# Raspberry-Board.net
KiCad netlist of a schematic drawn in EAGLE
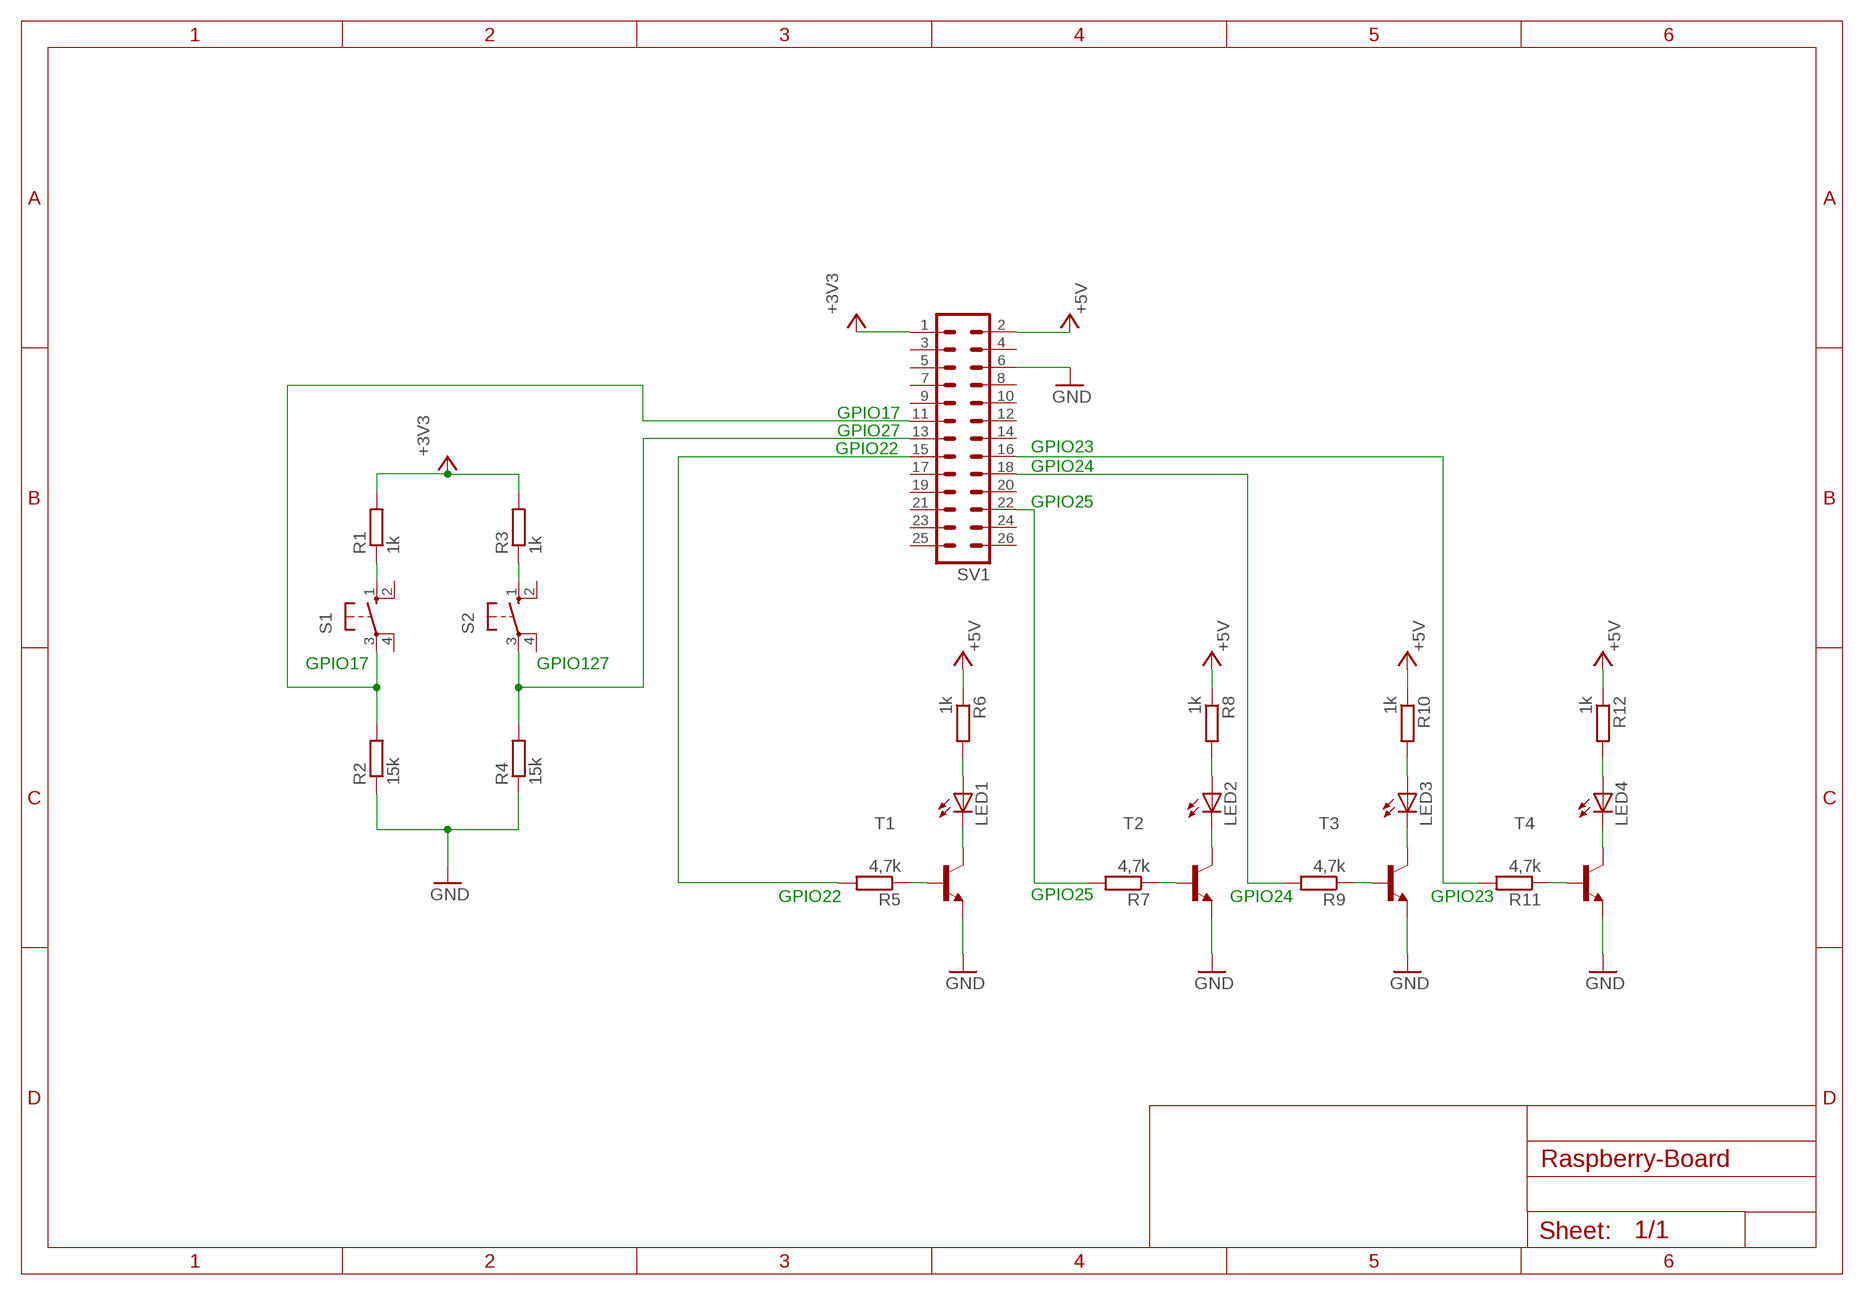
[diagram p0: schematic, sheet 1]

(export (version "E")
  (design (tool "Eeschema 10.0.6"))
  (components
    (comp (ref "LED1")
      (value "LEDCHIPLED_1206")
      (footprint "eagle-import:CHIPLED_1206")
      (libsource (lib "eagle-import") (part "LEDCHIPLED_1206"))
    )
    (comp (ref "LED2")
      (value "LEDCHIPLED_1206")
      (footprint "eagle-import:CHIPLED_1206")
      (libsource (lib "eagle-import") (part "LEDCHIPLED_1206"))
    )
    (comp (ref "LED3")
      (value "LEDCHIPLED_1206")
      (footprint "eagle-import:CHIPLED_1206")
      (libsource (lib "eagle-import") (part "LEDCHIPLED_1206"))
    )
    (comp (ref "LED4")
      (value "LEDCHIPLED_1206")
      (footprint "eagle-import:CHIPLED_1206")
      (libsource (lib "eagle-import") (part "LEDCHIPLED_1206"))
    )
    (comp (ref "R1")
      (value "1k")
      (footprint "eagle-import:R0805")
      (libsource (lib "eagle-import") (part "R-EU_R0805"))
    )
    (comp (ref "R2")
      (value "15k")
      (footprint "eagle-import:R0805")
      (libsource (lib "eagle-import") (part "R-EU_R0805"))
    )
    (comp (ref "R3")
      (value "1k")
      (footprint "eagle-import:R0805")
      (libsource (lib "eagle-import") (part "R-EU_R0805"))
    )
    (comp (ref "R4")
      (value "15k")
      (footprint "eagle-import:R0805")
      (libsource (lib "eagle-import") (part "R-EU_R0805"))
    )
    (comp (ref "R5")
      (value "4,7k")
      (footprint "eagle-import:R0805")
      (libsource (lib "eagle-import") (part "R-EU_R0805"))
    )
    (comp (ref "R6")
      (value "1k")
      (footprint "eagle-import:R0805")
      (libsource (lib "eagle-import") (part "R-EU_R0805"))
    )
    (comp (ref "R7")
      (value "4,7k")
      (footprint "eagle-import:R0805")
      (libsource (lib "eagle-import") (part "R-EU_R0805"))
    )
    (comp (ref "R8")
      (value "1k")
      (footprint "eagle-import:R0805")
      (libsource (lib "eagle-import") (part "R-EU_R0805"))
    )
    (comp (ref "R9")
      (value "4,7k")
      (footprint "eagle-import:R0805")
      (libsource (lib "eagle-import") (part "R-EU_R0805"))
    )
    (comp (ref "R10")
      (value "1k")
      (footprint "eagle-import:R0805")
      (libsource (lib "eagle-import") (part "R-EU_R0805"))
    )
    (comp (ref "R11")
      (value "4,7k")
      (footprint "eagle-import:R0805")
      (libsource (lib "eagle-import") (part "R-EU_R0805"))
    )
    (comp (ref "R12")
      (value "1k")
      (footprint "eagle-import:R0805")
      (libsource (lib "eagle-import") (part "R-EU_R0805"))
    )
    (comp (ref "S1")
      (value "10-XX")
      (footprint "eagle-import:B3F-10XX")
      (fields (field (name "MPN") "B3F-1000"))
      (libsource (lib "eagle-import") (part "10-XX"))
    )
    (comp (ref "S2")
      (value "10-XX")
      (footprint "eagle-import:B3F-10XX")
      (fields (field (name "MPN") "B3F-1000"))
      (libsource (lib "eagle-import") (part "10-XX"))
    )
    (comp (ref "SV1")
      (value "MA13-2")
      (footprint "eagle-import:MA13-2")
      (libsource (lib "eagle-import") (part "MA13-2"))
    )
    (comp (ref "T1")
      (value "BC817-16-NPN-SOT23-BEC")
      (footprint "eagle-import:SOT23-BEC")
      (libsource (lib "eagle-import") (part "-NPN-SOT23-BECBC817-16"))
    )
    (comp (ref "T2")
      (value "BC817-16-NPN-SOT23-BEC")
      (footprint "eagle-import:SOT23-BEC")
      (libsource (lib "eagle-import") (part "-NPN-SOT23-BECBC817-16"))
    )
    (comp (ref "T3")
      (value "BC817-16-NPN-SOT23-BEC")
      (footprint "eagle-import:SOT23-BEC")
      (libsource (lib "eagle-import") (part "-NPN-SOT23-BECBC817-16"))
    )
    (comp (ref "T4")
      (value "BC817-16-NPN-SOT23-BEC")
      (footprint "eagle-import:SOT23-BEC")
      (libsource (lib "eagle-import") (part "-NPN-SOT23-BECBC817-16"))
    )
  )
  (nets
    (net (code "1") (name "+3V3") (class "Default")
      (node (ref "R1") (pin "2") (pinfunction "2_2") (pintype "passive"))
      (node (ref "R3") (pin "2") (pinfunction "2_2") (pintype "passive"))
      (node (ref "SV1") (pin "1") (pinfunction "1_1") (pintype "passive"))
    )
    (net (code "2") (name "+5V") (class "Default")
      (node (ref "R10") (pin "1") (pinfunction "1_1") (pintype "passive"))
      (node (ref "R12") (pin "1") (pinfunction "1_1") (pintype "passive"))
      (node (ref "R6") (pin "1") (pinfunction "1_1") (pintype "passive"))
      (node (ref "R8") (pin "1") (pinfunction "1_1") (pintype "passive"))
      (node (ref "SV1") (pin "2") (pinfunction "2_2") (pintype "passive"))
    )
    (net (code "3") (name "GND") (class "Default")
      (node (ref "R2") (pin "1") (pinfunction "1_1") (pintype "passive"))
      (node (ref "R4") (pin "1") (pinfunction "1_1") (pintype "passive"))
      (node (ref "SV1") (pin "6") (pinfunction "6_6") (pintype "passive"))
      (node (ref "T1") (pin "E") (pinfunction "E_E") (pintype "passive"))
      (node (ref "T2") (pin "E") (pinfunction "E_E") (pintype "passive"))
      (node (ref "T3") (pin "E") (pinfunction "E_E") (pintype "passive"))
      (node (ref "T4") (pin "E") (pinfunction "E_E") (pintype "passive"))
    )
    (net (code "4") (name "Net-(LED1-PadA)") (class "Default")
      (node (ref "LED1") (pin "A") (pinfunction "A_A") (pintype "passive"))
      (node (ref "R6") (pin "2") (pinfunction "2_2") (pintype "passive"))
    )
    (net (code "5") (name "Net-(LED1-PadC)") (class "Default")
      (node (ref "LED1") (pin "C") (pinfunction "C_C") (pintype "passive"))
      (node (ref "T1") (pin "C") (pinfunction "C_C") (pintype "passive"))
    )
    (net (code "6") (name "Net-(LED2-PadA)") (class "Default")
      (node (ref "LED2") (pin "A") (pinfunction "A_A") (pintype "passive"))
      (node (ref "R8") (pin "2") (pinfunction "2_2") (pintype "passive"))
    )
    (net (code "7") (name "Net-(LED2-PadC)") (class "Default")
      (node (ref "LED2") (pin "C") (pinfunction "C_C") (pintype "passive"))
      (node (ref "T2") (pin "C") (pinfunction "C_C") (pintype "passive"))
    )
    (net (code "8") (name "Net-(LED3-PadA)") (class "Default")
      (node (ref "LED3") (pin "A") (pinfunction "A_A") (pintype "passive"))
      (node (ref "R10") (pin "2") (pinfunction "2_2") (pintype "passive"))
    )
    (net (code "9") (name "Net-(LED3-PadC)") (class "Default")
      (node (ref "LED3") (pin "C") (pinfunction "C_C") (pintype "passive"))
      (node (ref "T3") (pin "C") (pinfunction "C_C") (pintype "passive"))
    )
    (net (code "10") (name "Net-(LED4-PadA)") (class "Default")
      (node (ref "LED4") (pin "A") (pinfunction "A_A") (pintype "passive"))
      (node (ref "R12") (pin "2") (pinfunction "2_2") (pintype "passive"))
    )
    (net (code "11") (name "Net-(LED4-PadC)") (class "Default")
      (node (ref "LED4") (pin "C") (pinfunction "C_C") (pintype "passive"))
      (node (ref "T4") (pin "C") (pinfunction "C_C") (pintype "passive"))
    )
    (net (code "12") (name "Net-(R5-Pad1)") (class "Default")
      (node (ref "R5") (pin "1") (pinfunction "1_1") (pintype "passive"))
      (node (ref "T1") (pin "B") (pinfunction "B_B") (pintype "passive"))
    )
    (net (code "13") (name "Net-(R5-Pad2)") (class "Default")
      (node (ref "R5") (pin "2") (pinfunction "2_2") (pintype "passive"))
      (node (ref "SV1") (pin "15") (pinfunction "15_15") (pintype "passive"))
    )
    (net (code "14") (name "Net-(R7-Pad1)") (class "Default")
      (node (ref "R7") (pin "1") (pinfunction "1_1") (pintype "passive"))
      (node (ref "T2") (pin "B") (pinfunction "B_B") (pintype "passive"))
    )
    (net (code "15") (name "Net-(R7-Pad2)") (class "Default")
      (node (ref "R7") (pin "2") (pinfunction "2_2") (pintype "passive"))
      (node (ref "SV1") (pin "22") (pinfunction "22_22") (pintype "passive"))
    )
    (net (code "16") (name "Net-(R9-Pad1)") (class "Default")
      (node (ref "R9") (pin "1") (pinfunction "1_1") (pintype "passive"))
      (node (ref "T3") (pin "B") (pinfunction "B_B") (pintype "passive"))
    )
    (net (code "17") (name "Net-(R9-Pad2)") (class "Default")
      (node (ref "R9") (pin "2") (pinfunction "2_2") (pintype "passive"))
      (node (ref "SV1") (pin "18") (pinfunction "18_18") (pintype "passive"))
    )
    (net (code "18") (name "Net-(R11-Pad1)") (class "Default")
      (node (ref "R11") (pin "1") (pinfunction "1_1") (pintype "passive"))
      (node (ref "T4") (pin "B") (pinfunction "B_B") (pintype "passive"))
    )
    (net (code "19") (name "Net-(R11-Pad2)") (class "Default")
      (node (ref "R11") (pin "2") (pinfunction "2_2") (pintype "passive"))
      (node (ref "SV1") (pin "16") (pinfunction "16_16") (pintype "passive"))
    )
    (net (code "20") (name "Net-(S1-P)") (class "Default")
      (node (ref "R2") (pin "2") (pinfunction "2_2") (pintype "passive"))
      (node (ref "S1") (pin "3") (pinfunction "P_3") (pintype "passive"))
      (node (ref "SV1") (pin "11") (pinfunction "11_11") (pintype "passive"))
    )
    (net (code "21") (name "Net-(S1-S)") (class "Default")
      (node (ref "R1") (pin "1") (pinfunction "1_1") (pintype "passive"))
      (node (ref "S1") (pin "1") (pinfunction "S_1") (pintype "passive"))
    )
    (net (code "22") (name "Net-(S2-P)") (class "Default")
      (node (ref "R4") (pin "2") (pinfunction "2_2") (pintype "passive"))
      (node (ref "S2") (pin "3") (pinfunction "P_3") (pintype "passive"))
      (node (ref "SV1") (pin "13") (pinfunction "13_13") (pintype "passive"))
    )
    (net (code "23") (name "Net-(S2-S)") (class "Default")
      (node (ref "R3") (pin "1") (pinfunction "1_1") (pintype "passive"))
      (node (ref "S2") (pin "1") (pinfunction "S_1") (pintype "passive"))
    )
    (net (code "24") (name "unconnected-(S1-P1-Pad4)") (class "Default")
      (node (ref "S1") (pin "4") (pinfunction "P1_4") (pintype "passive"))
    )
    (net (code "25") (name "unconnected-(S1-S1-Pad2)") (class "Default")
      (node (ref "S1") (pin "2") (pinfunction "S1_2") (pintype "passive"))
    )
    (net (code "26") (name "unconnected-(S2-P1-Pad4)") (class "Default")
      (node (ref "S2") (pin "4") (pinfunction "P1_4") (pintype "passive"))
    )
    (net (code "27") (name "unconnected-(S2-S1-Pad2)") (class "Default")
      (node (ref "S2") (pin "2") (pinfunction "S1_2") (pintype "passive"))
    )
    (net (code "28") (name "unconnected-(SV1-Pad3)") (class "Default")
      (node (ref "SV1") (pin "3") (pinfunction "3_3") (pintype "passive"))
    )
    (net (code "29") (name "unconnected-(SV1-Pad4)") (class "Default")
      (node (ref "SV1") (pin "4") (pinfunction "4_4") (pintype "passive"))
    )
    (net (code "30") (name "unconnected-(SV1-Pad5)") (class "Default")
      (node (ref "SV1") (pin "5") (pinfunction "5_5") (pintype "passive"))
    )
    (net (code "31") (name "unconnected-(SV1-Pad7)") (class "Default")
      (node (ref "SV1") (pin "7") (pinfunction "7_7") (pintype "passive"))
    )
    (net (code "32") (name "unconnected-(SV1-Pad8)") (class "Default")
      (node (ref "SV1") (pin "8") (pinfunction "8_8") (pintype "passive"))
    )
    (net (code "33") (name "unconnected-(SV1-Pad9)") (class "Default")
      (node (ref "SV1") (pin "9") (pinfunction "9_9") (pintype "passive"))
    )
    (net (code "34") (name "unconnected-(SV1-Pad10)") (class "Default")
      (node (ref "SV1") (pin "10") (pinfunction "10_10") (pintype "passive"))
    )
    (net (code "35") (name "unconnected-(SV1-Pad12)") (class "Default")
      (node (ref "SV1") (pin "12") (pinfunction "12_12") (pintype "passive"))
    )
    (net (code "36") (name "unconnected-(SV1-Pad14)") (class "Default")
      (node (ref "SV1") (pin "14") (pinfunction "14_14") (pintype "passive"))
    )
    (net (code "37") (name "unconnected-(SV1-Pad17)") (class "Default")
      (node (ref "SV1") (pin "17") (pinfunction "17_17") (pintype "passive"))
    )
    (net (code "38") (name "unconnected-(SV1-Pad19)") (class "Default")
      (node (ref "SV1") (pin "19") (pinfunction "19_19") (pintype "passive"))
    )
    (net (code "39") (name "unconnected-(SV1-Pad20)") (class "Default")
      (node (ref "SV1") (pin "20") (pinfunction "20_20") (pintype "passive"))
    )
    (net (code "40") (name "unconnected-(SV1-Pad21)") (class "Default")
      (node (ref "SV1") (pin "21") (pinfunction "21_21") (pintype "passive"))
    )
    (net (code "41") (name "unconnected-(SV1-Pad23)") (class "Default")
      (node (ref "SV1") (pin "23") (pinfunction "23_23") (pintype "passive"))
    )
    (net (code "42") (name "unconnected-(SV1-Pad24)") (class "Default")
      (node (ref "SV1") (pin "24") (pinfunction "24_24") (pintype "passive"))
    )
    (net (code "43") (name "unconnected-(SV1-Pad25)") (class "Default")
      (node (ref "SV1") (pin "25") (pinfunction "25_25") (pintype "passive"))
    )
    (net (code "44") (name "unconnected-(SV1-Pad26)") (class "Default")
      (node (ref "SV1") (pin "26") (pinfunction "26_26") (pintype "passive"))
    )
  )
)
